# ADP5063.net
KiCad netlist of a schematic drawn in EAGLE
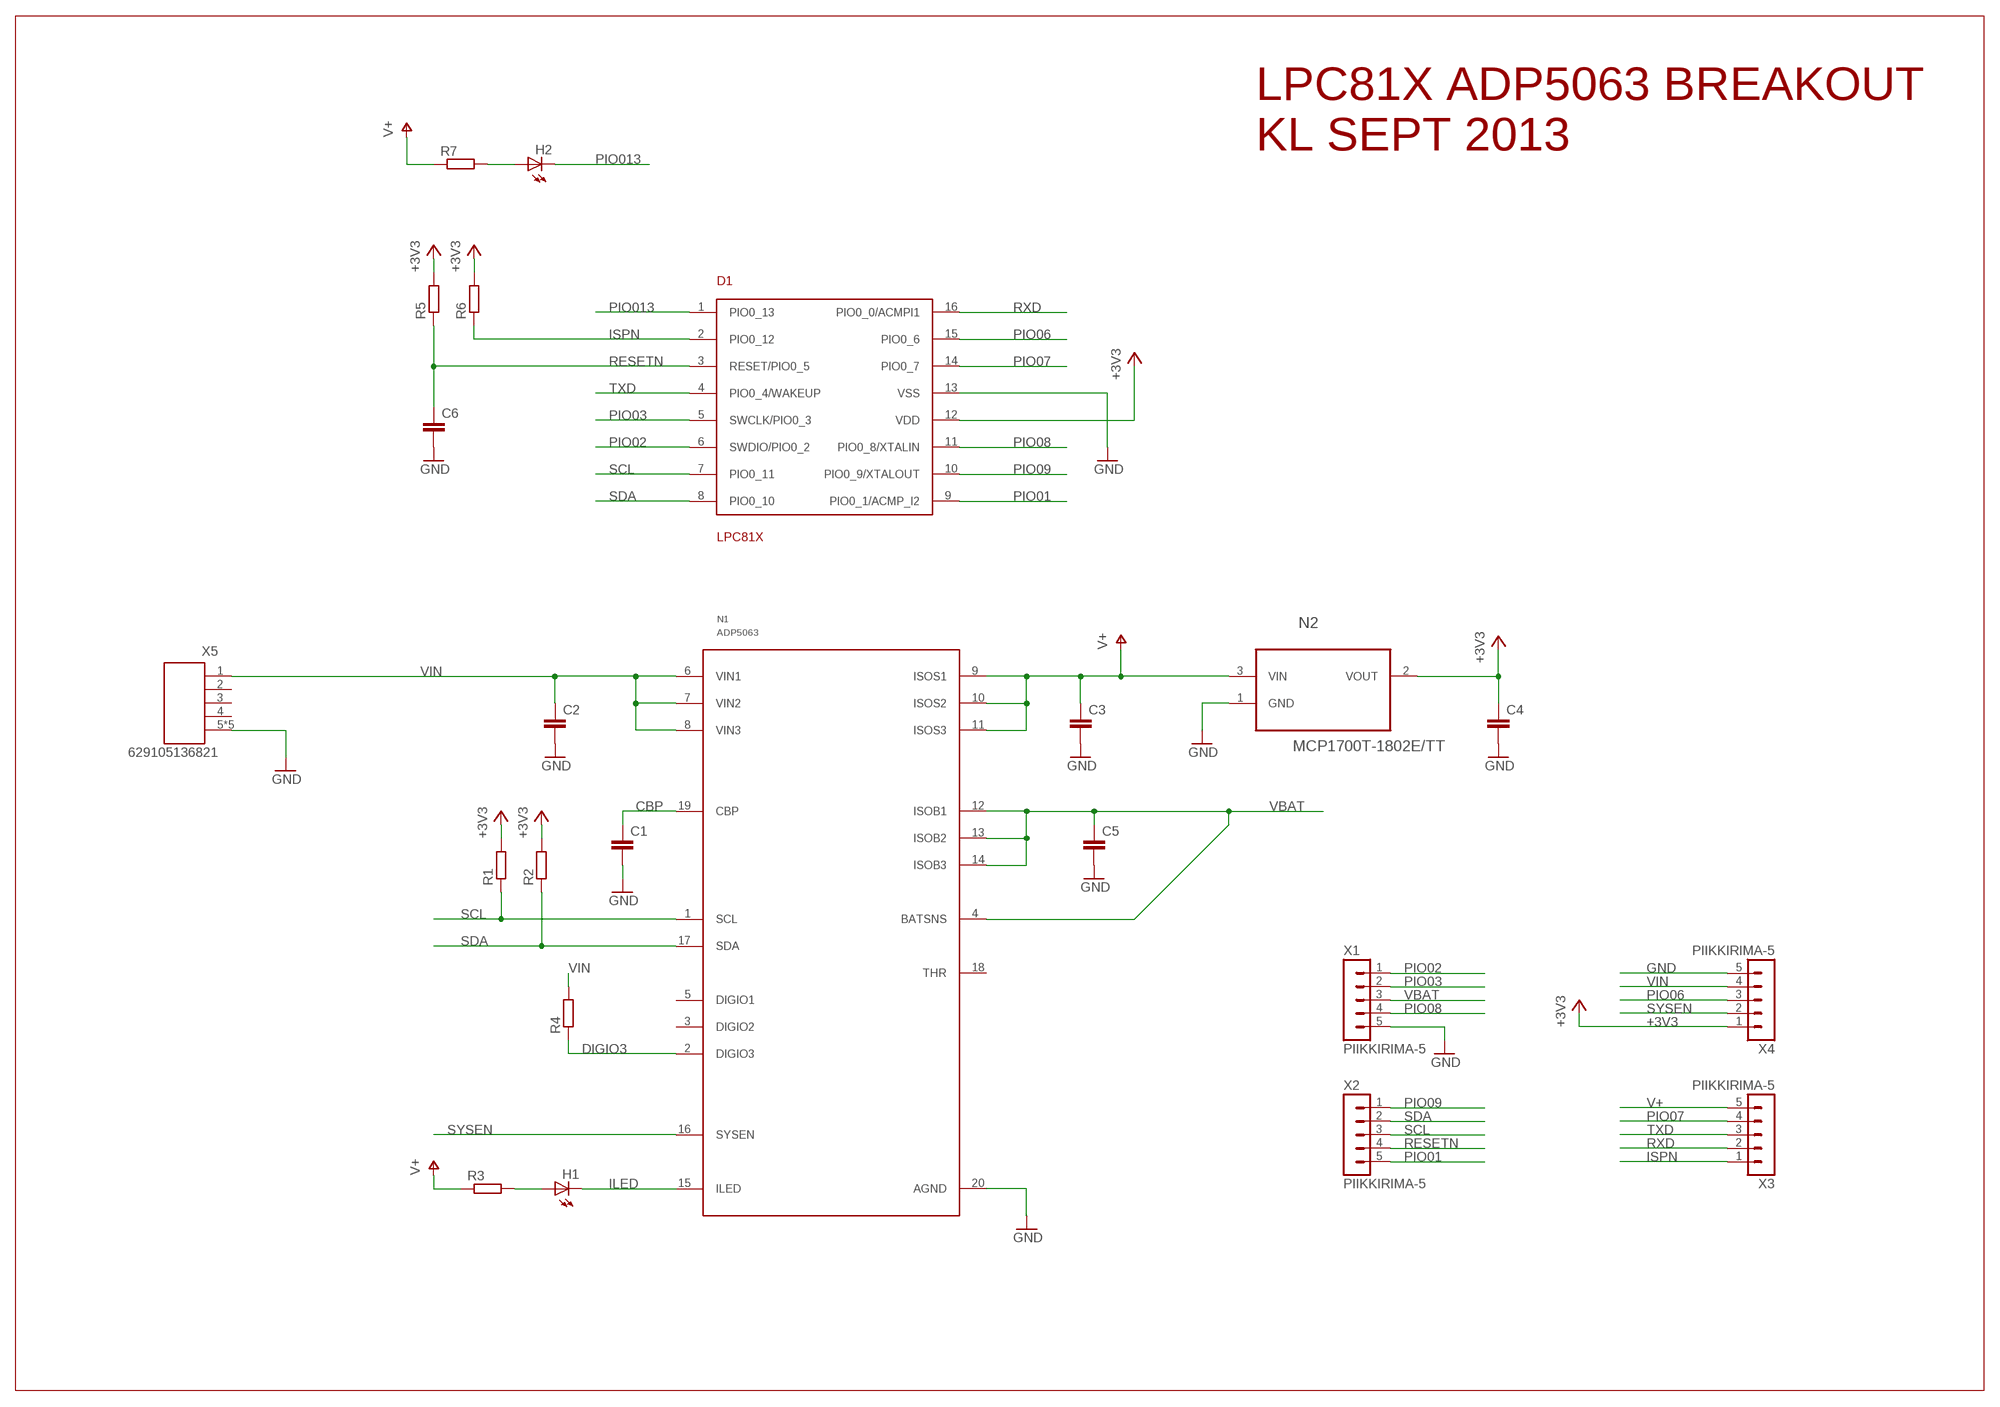
[diagram p0: schematic, sheet 1]

(export (version "E")
  (design (tool "Eeschema 10.0.6"))
  (components
    (comp (ref "C1")
      (value "C-EUC0603")
      (footprint "eagle-import:C0603")
      (libsource (lib "eagle-import") (part "C-EUC0603"))
    )
    (comp (ref "C2")
      (value "C-EUC1206")
      (footprint "eagle-import:C1206")
      (libsource (lib "eagle-import") (part "C-EUC1206"))
    )
    (comp (ref "C3")
      (value "C-EUC1206")
      (footprint "eagle-import:C1206")
      (libsource (lib "eagle-import") (part "C-EUC1206"))
    )
    (comp (ref "C4")
      (value "C-EUC1206")
      (footprint "eagle-import:C1206")
      (libsource (lib "eagle-import") (part "C-EUC1206"))
    )
    (comp (ref "C5")
      (value "C-EUC1206")
      (footprint "eagle-import:C1206")
      (libsource (lib "eagle-import") (part "C-EUC1206"))
    )
    (comp (ref "C6")
      (value "C-EUC0603")
      (footprint "eagle-import:C0603")
      (libsource (lib "eagle-import") (part "C-EUC0603"))
    )
    (comp (ref "D1")
      (value "LPC81X")
      (footprint "eagle-import:TSSOP16")
      (libsource (lib "eagle-import") (part "LPC81X"))
    )
    (comp (ref "H1")
      (value "LEDCHIP-LED0603")
      (footprint "eagle-import:CHIP-LED0603")
      (libsource (lib "eagle-import") (part "LEDCHIP-LED0603"))
    )
    (comp (ref "H2")
      (value "LEDCHIP-LED0603")
      (footprint "eagle-import:CHIP-LED0603")
      (libsource (lib "eagle-import") (part "LEDCHIP-LED0603"))
    )
    (comp (ref "N1")
      (value "ADP5063")
      (footprint "eagle-import:QFN50P400X400X80-21N")
      (libsource (lib "eagle-import") (part "ADP5063"))
    )
    (comp (ref "N2")
      (value "MCP1700T-1802E/TT")
      (footprint "eagle-import:SOT95P237X112-3N")
      (libsource (lib "eagle-import") (part "MCP1700T-1802E/TT"))
    )
    (comp (ref "R1")
      (value "R-EU_R0603")
      (footprint "eagle-import:R0603")
      (libsource (lib "eagle-import") (part "R-EU_R0603"))
    )
    (comp (ref "R2")
      (value "R-EU_R0603")
      (footprint "eagle-import:R0603")
      (libsource (lib "eagle-import") (part "R-EU_R0603"))
    )
    (comp (ref "R3")
      (value "R-EU_R0603")
      (footprint "eagle-import:R0603")
      (libsource (lib "eagle-import") (part "R-EU_R0603"))
    )
    (comp (ref "R4")
      (value "R-EU_R0603")
      (footprint "eagle-import:R0603")
      (libsource (lib "eagle-import") (part "R-EU_R0603"))
    )
    (comp (ref "R5")
      (value "R-EU_R0603")
      (footprint "eagle-import:R0603")
      (libsource (lib "eagle-import") (part "R-EU_R0603"))
    )
    (comp (ref "R6")
      (value "R-EU_R0603")
      (footprint "eagle-import:R0603")
      (libsource (lib "eagle-import") (part "R-EU_R0603"))
    )
    (comp (ref "R7")
      (value "R-EU_R0603")
      (footprint "eagle-import:R0603")
      (libsource (lib "eagle-import") (part "R-EU_R0603"))
    )
    (comp (ref "X1")
      (value "PIIKKIRIMA-5")
      (footprint "eagle-import:PIIKKIRIMA-5")
      (libsource (lib "eagle-import") (part "PIIKKIRIMA-5"))
    )
    (comp (ref "X2")
      (value "PIIKKIRIMA-5")
      (footprint "eagle-import:PIIKKIRIMA-5")
      (libsource (lib "eagle-import") (part "PIIKKIRIMA-5"))
    )
    (comp (ref "X3")
      (value "PIIKKIRIMA-5")
      (footprint "eagle-import:PIIKKIRIMA-5")
      (libsource (lib "eagle-import") (part "PIIKKIRIMA-5"))
    )
    (comp (ref "X4")
      (value "PIIKKIRIMA-5")
      (footprint "eagle-import:PIIKKIRIMA-5")
      (libsource (lib "eagle-import") (part "PIIKKIRIMA-5"))
    )
    (comp (ref "X5")
      (value "629105136821")
      (footprint "eagle-import:629105136821")
      (libsource (lib "eagle-import") (part "629105136821"))
    )
  )
  (nets
    (net (code "1") (name "+3V3") (class "Default")
      (node (ref "C4") (pin "1") (pinfunction "1_1") (pintype "passive"))
      (node (ref "D1") (pin "12") (pinfunction "VDD_12") (pintype "bidirectional"))
      (node (ref "N2") (pin "2") (pinfunction "VOUT_2") (pintype "output"))
      (node (ref "R1") (pin "2") (pinfunction "2_2") (pintype "passive"))
      (node (ref "R2") (pin "2") (pinfunction "2_2") (pintype "passive"))
      (node (ref "R5") (pin "2") (pinfunction "2_2") (pintype "passive"))
      (node (ref "R6") (pin "2") (pinfunction "2_2") (pintype "passive"))
      (node (ref "X4") (pin "1") (pinfunction "1_1") (pintype "passive"))
    )
    (net (code "2") (name "/CBP") (class "Default")
      (node (ref "C1") (pin "1") (pinfunction "1_1") (pintype "passive"))
      (node (ref "N1") (pin "19") (pinfunction "CBP_19") (pintype "bidirectional"))
    )
    (net (code "3") (name "/DIGIO3") (class "Default")
      (node (ref "N1") (pin "2") (pinfunction "DIGIO3_2") (pintype "bidirectional"))
      (node (ref "R4") (pin "1") (pinfunction "1_1") (pintype "passive"))
    )
    (net (code "4") (name "/ILED") (class "Default")
      (node (ref "H1") (pin "C") (pinfunction "C_C") (pintype "passive"))
      (node (ref "N1") (pin "15") (pinfunction "ILED_15") (pintype "bidirectional"))
    )
    (net (code "5") (name "/ISPN") (class "Default")
      (node (ref "D1") (pin "2") (pinfunction "PIO0_12_2") (pintype "bidirectional"))
      (node (ref "R6") (pin "1") (pinfunction "1_1") (pintype "passive"))
      (node (ref "X3") (pin "1") (pinfunction "1_1") (pintype "passive"))
    )
    (net (code "6") (name "/PIO01") (class "Default")
      (node (ref "D1") (pin "9") (pinfunction "PIO0_1/ACMP_I2_9") (pintype "bidirectional"))
      (node (ref "X2") (pin "5") (pinfunction "5_5") (pintype "passive"))
    )
    (net (code "7") (name "/PIO02") (class "Default")
      (node (ref "D1") (pin "6") (pinfunction "SWDIO/PIO0_2_6") (pintype "bidirectional"))
      (node (ref "X1") (pin "1") (pinfunction "1_1") (pintype "passive"))
    )
    (net (code "8") (name "/PIO03") (class "Default")
      (node (ref "D1") (pin "5") (pinfunction "SWCLK/PIO0_3_5") (pintype "bidirectional"))
      (node (ref "X1") (pin "2") (pinfunction "2_2") (pintype "passive"))
    )
    (net (code "9") (name "/PIO06") (class "Default")
      (node (ref "D1") (pin "15") (pinfunction "PIO0_6_15") (pintype "bidirectional"))
      (node (ref "X4") (pin "3") (pinfunction "3_3") (pintype "passive"))
    )
    (net (code "10") (name "/PIO07") (class "Default")
      (node (ref "D1") (pin "14") (pinfunction "PIO0_7_14") (pintype "bidirectional"))
      (node (ref "X3") (pin "4") (pinfunction "4_4") (pintype "passive"))
    )
    (net (code "11") (name "/PIO08") (class "Default")
      (node (ref "D1") (pin "11") (pinfunction "PIO0_8/XTALIN_11") (pintype "bidirectional"))
      (node (ref "X1") (pin "4") (pinfunction "4_4") (pintype "passive"))
    )
    (net (code "12") (name "/PIO09") (class "Default")
      (node (ref "D1") (pin "10") (pinfunction "PIO0_9/XTALOUT_10") (pintype "bidirectional"))
      (node (ref "X2") (pin "1") (pinfunction "1_1") (pintype "passive"))
    )
    (net (code "13") (name "/PIO013") (class "Default")
      (node (ref "D1") (pin "1") (pinfunction "PIO0_13_1") (pintype "bidirectional"))
      (node (ref "H2") (pin "C") (pinfunction "C_C") (pintype "passive"))
    )
    (net (code "14") (name "/RESETN") (class "Default")
      (node (ref "C6") (pin "1") (pinfunction "1_1") (pintype "passive"))
      (node (ref "D1") (pin "3") (pinfunction "RESET/PIO0_5_3") (pintype "bidirectional"))
      (node (ref "R5") (pin "1") (pinfunction "1_1") (pintype "passive"))
      (node (ref "X2") (pin "4") (pinfunction "4_4") (pintype "passive"))
    )
    (net (code "15") (name "/RXD") (class "Default")
      (node (ref "D1") (pin "16") (pinfunction "PIO0_0/ACMPI1_16") (pintype "bidirectional"))
      (node (ref "X3") (pin "2") (pinfunction "2_2") (pintype "passive"))
    )
    (net (code "16") (name "/SCL") (class "Default")
      (node (ref "D1") (pin "7") (pinfunction "PIO0_11_7") (pintype "bidirectional"))
      (node (ref "N1") (pin "1") (pinfunction "SCL_1") (pintype "bidirectional"))
      (node (ref "R1") (pin "1") (pinfunction "1_1") (pintype "passive"))
      (node (ref "X2") (pin "3") (pinfunction "3_3") (pintype "passive"))
    )
    (net (code "17") (name "/SDA") (class "Default")
      (node (ref "D1") (pin "8") (pinfunction "PIO0_10_8") (pintype "bidirectional"))
      (node (ref "N1") (pin "17") (pinfunction "SDA_17") (pintype "bidirectional"))
      (node (ref "R2") (pin "1") (pinfunction "1_1") (pintype "passive"))
      (node (ref "X2") (pin "2") (pinfunction "2_2") (pintype "passive"))
    )
    (net (code "18") (name "/SYSEN") (class "Default")
      (node (ref "N1") (pin "16") (pinfunction "SYSEN_16") (pintype "bidirectional"))
      (node (ref "X4") (pin "2") (pinfunction "2_2") (pintype "passive"))
    )
    (net (code "19") (name "/TXD") (class "Default")
      (node (ref "D1") (pin "4") (pinfunction "PIO0_4/WAKEUP_4") (pintype "bidirectional"))
      (node (ref "X3") (pin "3") (pinfunction "3_3") (pintype "passive"))
    )
    (net (code "20") (name "/VBAT") (class "Default")
      (node (ref "C5") (pin "1") (pinfunction "1_1") (pintype "passive"))
      (node (ref "N1") (pin "12") (pinfunction "ISOB1_12") (pintype "bidirectional"))
      (node (ref "N1") (pin "13") (pinfunction "ISOB2_13") (pintype "bidirectional"))
      (node (ref "N1") (pin "14") (pinfunction "ISOB3_14") (pintype "bidirectional"))
      (node (ref "N1") (pin "4") (pinfunction "BATSNS_4") (pintype "bidirectional"))
      (node (ref "X1") (pin "3") (pinfunction "3_3") (pintype "passive"))
    )
    (net (code "21") (name "/VIN") (class "Default")
      (node (ref "C2") (pin "1") (pinfunction "1_1") (pintype "passive"))
      (node (ref "N1") (pin "6") (pinfunction "VIN1_6") (pintype "bidirectional"))
      (node (ref "N1") (pin "7") (pinfunction "VIN2_7") (pintype "bidirectional"))
      (node (ref "N1") (pin "8") (pinfunction "VIN3_8") (pintype "bidirectional"))
      (node (ref "R4") (pin "2") (pinfunction "2_2") (pintype "passive"))
      (node (ref "X4") (pin "4") (pinfunction "4_4") (pintype "passive"))
      (node (ref "X5") (pin "1") (pinfunction "1_1") (pintype "passive"))
    )
    (net (code "22") (name "GND") (class "Default")
      (node (ref "C1") (pin "2") (pinfunction "2_2") (pintype "passive"))
      (node (ref "C2") (pin "2") (pinfunction "2_2") (pintype "passive"))
      (node (ref "C3") (pin "2") (pinfunction "2_2") (pintype "passive"))
      (node (ref "C4") (pin "2") (pinfunction "2_2") (pintype "passive"))
      (node (ref "C5") (pin "2") (pinfunction "2_2") (pintype "passive"))
      (node (ref "C6") (pin "2") (pinfunction "2_2") (pintype "passive"))
      (node (ref "D1") (pin "13") (pinfunction "VSS_13") (pintype "bidirectional"))
      (node (ref "N1") (pin "20") (pinfunction "AGND_20") (pintype "bidirectional"))
      (node (ref "N2") (pin "1") (pinfunction "GND_1") (pintype "passive"))
      (node (ref "X1") (pin "5") (pinfunction "5_5") (pintype "passive"))
      (node (ref "X4") (pin "5") (pinfunction "5_5") (pintype "passive"))
      (node (ref "X5") (pin "5") (pinfunction "5_5") (pintype "passive"))
      (node (ref "X5") (pin "Z1") (pinfunction "5_Z1") (pintype "passive"))
      (node (ref "X5") (pin "Z2") (pinfunction "5_Z2") (pintype "passive"))
      (node (ref "X5") (pin "Z3") (pinfunction "5_Z3") (pintype "passive"))
      (node (ref "X5") (pin "Z4") (pinfunction "5_Z4") (pintype "passive"))
    )
    (net (code "23") (name "Net-(H1-PadA)") (class "Default")
      (node (ref "H1") (pin "A") (pinfunction "A_A") (pintype "passive"))
      (node (ref "R3") (pin "2") (pinfunction "2_2") (pintype "passive"))
    )
    (net (code "24") (name "Net-(H2-PadA)") (class "Default")
      (node (ref "H2") (pin "A") (pinfunction "A_A") (pintype "passive"))
      (node (ref "R7") (pin "2") (pinfunction "2_2") (pintype "passive"))
    )
    (net (code "25") (name "V+") (class "Default")
      (node (ref "C3") (pin "1") (pinfunction "1_1") (pintype "passive"))
      (node (ref "N1") (pin "10") (pinfunction "ISOS2_10") (pintype "bidirectional"))
      (node (ref "N1") (pin "11") (pinfunction "ISOS3_11") (pintype "bidirectional"))
      (node (ref "N1") (pin "9") (pinfunction "ISOS1_9") (pintype "bidirectional"))
      (node (ref "N2") (pin "3") (pinfunction "VIN_3") (pintype "input"))
      (node (ref "R3") (pin "1") (pinfunction "1_1") (pintype "passive"))
      (node (ref "R7") (pin "1") (pinfunction "1_1") (pintype "passive"))
      (node (ref "X3") (pin "5") (pinfunction "5_5") (pintype "passive"))
    )
    (net (code "26") (name "unconnected-(N1-DIGIO1-Pad5)") (class "Default")
      (node (ref "N1") (pin "5") (pinfunction "DIGIO1_5") (pintype "bidirectional"))
    )
    (net (code "27") (name "unconnected-(N1-DIGIO2-Pad3)") (class "Default")
      (node (ref "N1") (pin "3") (pinfunction "DIGIO2_3") (pintype "bidirectional"))
    )
    (net (code "28") (name "unconnected-(N1-THR-Pad18)") (class "Default")
      (node (ref "N1") (pin "18") (pinfunction "THR_18") (pintype "bidirectional"))
    )
    (net (code "29") (name "unconnected-(X5-Pad2)") (class "Default")
      (node (ref "X5") (pin "2") (pinfunction "2_2") (pintype "passive"))
    )
    (net (code "30") (name "unconnected-(X5-Pad3)") (class "Default")
      (node (ref "X5") (pin "3") (pinfunction "3_3") (pintype "passive"))
    )
    (net (code "31") (name "unconnected-(X5-Pad4)") (class "Default")
      (node (ref "X5") (pin "4") (pinfunction "4_4") (pintype "passive"))
    )
  )
)
